# ESP32-C3_DEV-M-1.net
KiCad netlist of a schematic drawn in Altium Designer
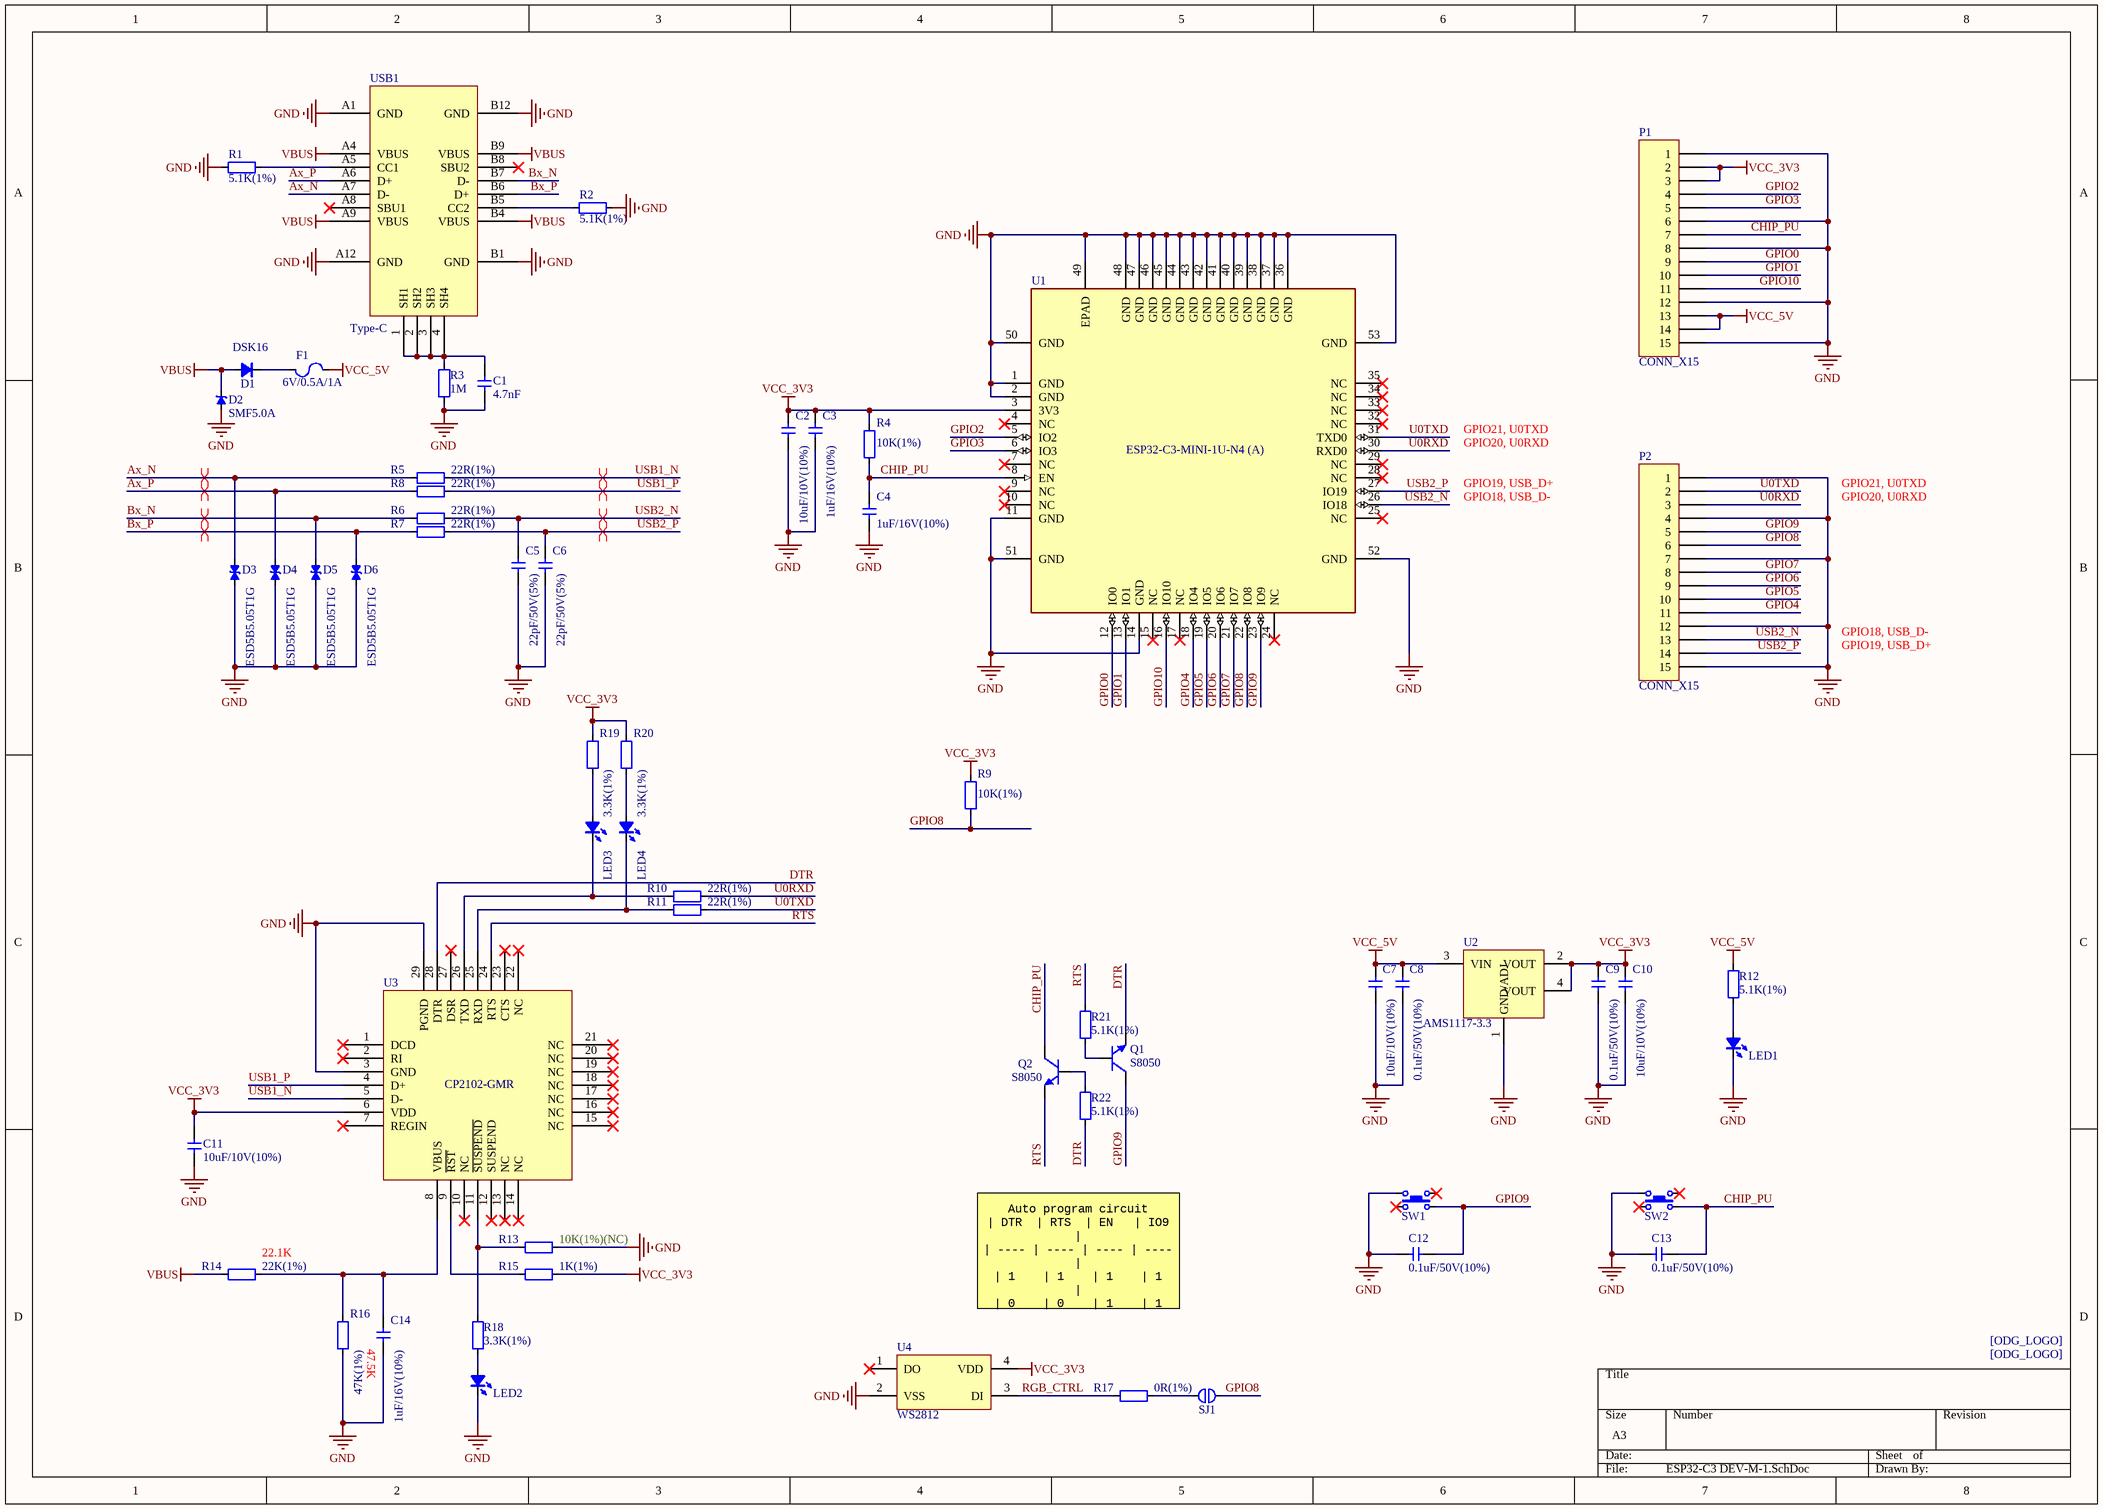
[diagram p0: ESP32-C3 DEV-M-1.SchDoc]

(export (version "E")
  (design (tool "Eeschema 10.0.6"))
  (components
    (comp (ref "C1")
      (value "4.7nF")
      (footprint "C0402")
      (description "Capacitor")
      (libsource (lib "ODG_AD_Lib") (part "CAP"))
    )
    (comp (ref "C2")
      (value "10uF/10V(10%)")
      (footprint "C0603")
      (description "Capacitor")
      (libsource (lib "ODG_AD_Lib") (part "CAP"))
    )
    (comp (ref "C3")
      (value "1uF/16V(10%)")
      (footprint "C0402")
      (description "Capacitor")
      (libsource (lib "ODG_AD_Lib") (part "CAP"))
    )
    (comp (ref "C4")
      (value "1uF/16V(10%)")
      (footprint "C0402")
      (description "Capacitor")
      (libsource (lib "ODG_AD_Lib") (part "CAP"))
    )
    (comp (ref "C5")
      (value "22pF/50V(5%)")
      (footprint "C0402")
      (description "Capacitor")
      (libsource (lib "ODG_AD_Lib") (part "CAP"))
    )
    (comp (ref "C6")
      (value "22pF/50V(5%)")
      (footprint "C0402")
      (description "Capacitor")
      (libsource (lib "ODG_AD_Lib") (part "CAP"))
    )
    (comp (ref "C7")
      (value "10uF/10V(10%)")
      (footprint "C0603")
      (description "Capacitor")
      (libsource (lib "ODG_AD_Lib") (part "CAP"))
    )
    (comp (ref "C8")
      (value "0.1uF/50V(10%)")
      (footprint "C0402")
      (description "Capacitor")
      (libsource (lib "ODG_AD_Lib") (part "CAP"))
    )
    (comp (ref "C9")
      (value "0.1uF/50V(10%)")
      (footprint "C0402")
      (description "Capacitor")
      (libsource (lib "ODG_AD_Lib") (part "CAP"))
    )
    (comp (ref "C10")
      (value "10uF/10V(10%)")
      (footprint "C0603")
      (description "Capacitor")
      (libsource (lib "ODG_AD_Lib") (part "CAP"))
    )
    (comp (ref "C11")
      (value "10uF/10V(10%)")
      (footprint "C0603")
      (description "Capacitor")
      (libsource (lib "ODG_AD_Lib") (part "CAP"))
    )
    (comp (ref "C12")
      (value "0.1uF/50V(10%)")
      (footprint "C0402")
      (description "Capacitor")
      (libsource (lib "ODG_AD_Lib") (part "CAP"))
    )
    (comp (ref "C13")
      (value "0.1uF/50V(10%)")
      (footprint "C0402")
      (description "Capacitor")
      (libsource (lib "ODG_AD_Lib") (part "CAP"))
    )
    (comp (ref "C14")
      (value "1uF/16V(10%)")
      (footprint "C0402")
      (description "Capacitor")
      (libsource (lib "ODG_AD_Lib") (part "CAP"))
    )
    (comp (ref "D1")
      (value "DSK16")
      (footprint "SOD123F")
      (description "二极管")
      (libsource (lib "ODG_AD_Lib") (part "DIODE"))
    )
    (comp (ref "D2")
      (value "SMF5.0A")
      (footprint "SOD123F")
      (description "极性：Unidirectional")
      (fields
        (field (name "MF") "Taiwan Semiconductor Corporation")
        (field (name "DIGI-KEY_PART_NUMBER") "TESD5V0L1UCRJGTR-ND")
      )
      (libsource (lib "ODG_AD_Lib") (part "TVS_U"))
    )
    (comp (ref "D3")
      (value "ESD5B5.05T1G")
      (footprint "SOD-523")
      (description "极性：Bidirectional")
      (fields
        (field (name "MF") "Taiwan Semiconductor Corporation")
        (field (name "DIGI-KEY_PART_NUMBER") "TESD5V0L1UCRJGTR-ND")
      )
      (libsource (lib "ODG_AD_Lib") (part "TVS_BI"))
    )
    (comp (ref "D4")
      (value "ESD5B5.05T1G")
      (footprint "SOD-523")
      (description "极性：Bidirectional")
      (fields
        (field (name "MF") "Taiwan Semiconductor Corporation")
        (field (name "DIGI-KEY_PART_NUMBER") "TESD5V0L1UCRJGTR-ND")
      )
      (libsource (lib "ODG_AD_Lib") (part "TVS_BI"))
    )
    (comp (ref "D5")
      (value "ESD5B5.05T1G")
      (footprint "SOD-523")
      (description "极性：Bidirectional")
      (fields
        (field (name "MF") "Taiwan Semiconductor Corporation")
        (field (name "DIGI-KEY_PART_NUMBER") "TESD5V0L1UCRJGTR-ND")
      )
      (libsource (lib "ODG_AD_Lib") (part "TVS_BI"))
    )
    (comp (ref "D6")
      (value "ESD5B5.05T1G")
      (footprint "SOD-523")
      (description "极性：Bidirectional")
      (fields
        (field (name "MF") "Taiwan Semiconductor Corporation")
        (field (name "DIGI-KEY_PART_NUMBER") "TESD5V0L1UCRJGTR-ND")
      )
      (libsource (lib "ODG_AD_Lib") (part "TVS_BI"))
    )
    (comp (ref "F1")
      (value "6V/0.5A/1A")
      (footprint "FUSE0603_0.5MM")
      (description "贴片自恢复保险丝")
      (libsource (lib "ODG_AD_Lib") (part "FUSE"))
    )
    (comp (ref "LED1") (value "LED") (footprint "LED0603_RED") (libsource (lib "ODG_AD_Lib") (part "LED")))
    (comp (ref "LED2") (value "LED") (footprint "LED0603_RED") (libsource (lib "ODG_AD_Lib") (part "LED")))
    (comp (ref "LED3") (value "LED") (footprint "LED0603_RED") (libsource (lib "ODG_AD_Lib") (part "LED")))
    (comp (ref "LED4") (value "LED") (footprint "LED0603_RED") (libsource (lib "ODG_AD_Lib") (part "LED")))
    (comp (ref "ODG1")
      (value "ODG_LOGO")
      (footprint "ODG_LOGO")
      (libsource (lib "ODG_AD_Lib") (part "ODG_LOGO"))
    )
    (comp (ref "ODG2")
      (value "ODG_LOGO")
      (footprint "ODG_LOGO")
      (libsource (lib "ODG_AD_Lib") (part "ODG_LOGO"))
    )
    (comp (ref "P1")
      (value "CONN_X15")
      (footprint "2.54MM_MALE_X15")
      (libsource (lib "ODG_AD_Lib") (part "CONN_X15"))
    )
    (comp (ref "P2")
      (value "CONN_X15")
      (footprint "2.54MM_MALE_X15")
      (libsource (lib "ODG_AD_Lib") (part "CONN_X15"))
    )
    (comp (ref "Q1")
      (value "S8050")
      (footprint "INFINEON SOT-23-3")
      (description "NPN型")
      (libsource (lib "ODG_AD_Lib") (part "NPN"))
    )
    (comp (ref "Q2")
      (value "S8050")
      (footprint "INFINEON SOT-23-3")
      (description "NPN型")
      (libsource (lib "ODG_AD_Lib") (part "NPN"))
    )
    (comp (ref "R1")
      (value "5.1K(1%)")
      (footprint "R0402")
      (description "Resistor")
      (libsource (lib "") (part "RES_1"))
    )
    (comp (ref "R2")
      (value "5.1K(1%)")
      (footprint "R0402")
      (description "Resistor")
      (libsource (lib "") (part "RES_1"))
    )
    (comp (ref "R3")
      (value "1M")
      (footprint "R0402")
      (description "Resistor")
      (libsource (lib "ODG_AD_Lib") (part "RES"))
    )
    (comp (ref "R4")
      (value "10K(1%)")
      (footprint "R0402")
      (description "Resistor")
      (libsource (lib "") (part "RES_1"))
    )
    (comp (ref "R5")
      (value "22R(1%)")
      (footprint "R0402")
      (description "Resistor")
      (libsource (lib "ODG_AD_Lib") (part "RES"))
    )
    (comp (ref "R6")
      (value "22R(1%)")
      (footprint "R0402")
      (description "Resistor")
      (libsource (lib "ODG_AD_Lib") (part "RES"))
    )
    (comp (ref "R7")
      (value "22R(1%)")
      (footprint "R0402")
      (description "Resistor")
      (libsource (lib "ODG_AD_Lib") (part "RES"))
    )
    (comp (ref "R8")
      (value "22R(1%)")
      (footprint "R0402")
      (description "Resistor")
      (libsource (lib "ODG_AD_Lib") (part "RES"))
    )
    (comp (ref "R9")
      (value "10K(1%)")
      (footprint "R0402")
      (description "Resistor")
      (libsource (lib "") (part "RES_1"))
    )
    (comp (ref "R10")
      (value "22R(1%)")
      (footprint "R0402")
      (description "Resistor")
      (libsource (lib "ODG_AD_Lib") (part "RES"))
    )
    (comp (ref "R11")
      (value "22R(1%)")
      (footprint "R0402")
      (description "Resistor")
      (libsource (lib "ODG_AD_Lib") (part "RES"))
    )
    (comp (ref "R12")
      (value "5.1K(1%)")
      (footprint "R0402")
      (description "Resistor")
      (libsource (lib "") (part "RES_1"))
    )
    (comp (ref "R13")
      (value "10K(1%)(NC)")
      (footprint "R0402")
      (description "Resistor")
      (libsource (lib "ODG_AD_Lib") (part "RES"))
    )
    (comp (ref "R14")
      (value "22K(1%)")
      (footprint "R0402")
      (description "Resistor")
      (libsource (lib "ODG_AD_Lib") (part "RES"))
    )
    (comp (ref "R15")
      (value "1K(1%)")
      (footprint "R0402")
      (description "Resistor")
      (libsource (lib "ODG_AD_Lib") (part "RES"))
    )
    (comp (ref "R16")
      (value "47K(1%)")
      (footprint "R0402")
      (description "Resistor")
      (libsource (lib "") (part "RES_1"))
    )
    (comp (ref "R17")
      (value "0R(1%)")
      (footprint "R0402")
      (description "Resistor")
      (libsource (lib "ODG_AD_Lib") (part "RES"))
    )
    (comp (ref "R18")
      (value "3.3K(1%)")
      (footprint "R0402")
      (description "Resistor")
      (libsource (lib "") (part "RES_1"))
    )
    (comp (ref "R19")
      (value "3.3K(1%)")
      (footprint "R0402")
      (description "Resistor")
      (libsource (lib "") (part "RES_1"))
    )
    (comp (ref "R20")
      (value "3.3K(1%)")
      (footprint "R0402")
      (description "Resistor")
      (libsource (lib "") (part "RES_1"))
    )
    (comp (ref "R21")
      (value "5.1K(1%)")
      (footprint "R0402")
      (description "Resistor")
      (libsource (lib "") (part "RES_1"))
    )
    (comp (ref "R22")
      (value "5.1K(1%)")
      (footprint "R0402")
      (description "Resistor")
      (libsource (lib "") (part "RES_1"))
    )
    (comp (ref "SJ1")
      (value "SJ_2P")
      (footprint "SJ_2P_MINI")
      (description "焊接跳线")
      (libsource (lib "ODG_AD_Lib") (part "SJ_2P"))
    )
    (comp (ref "SW1")
      (value "Button-4P")
      (footprint "SWITCH_3X4X2.5_4PIN_SMD")
      (description "Button")
      (libsource (lib "ODG_AD_Lib") (part "Button-4P"))
    )
    (comp (ref "SW2")
      (value "Button-4P")
      (footprint "SWITCH_3X4X2.5_4PIN_SMD")
      (description "Button")
      (libsource (lib "ODG_AD_Lib") (part "Button-4P"))
    )
    (comp (ref "U1")
      (value "ESP32-C3-MINI-1U-N4 (A)")
      (footprint "XCVR_ESP32-C3-MINI-1U-N4")
      (fields
        (field (name "MF") "Espressif Systems")
        (field (name "DIGI-KEY_PART_NUMBER") "1965-ESP32-C3-MINI-1U-N4TR-ND")
        (field (name "MP") "ESP32-C3-MINI-1U-N4")
      )
      (libsource (lib "ODG_AD_Lib") (part "ESP32-C3-MINI-1U-N4 (A)"))
    )
    (comp (ref "U2")
      (value "AMS1117-3.3")
      (footprint "TI SOT-223 DCY")
      (description "线性稳压芯片")
      (libsource (lib "ODG_AD_Lib") (part "AMS1117"))
    )
    (comp (ref "U3")
      (value "CP2102-GMR")
      (footprint "QFN-28_EP")
      (description "USB转TTL")
      (fields (field (name "PART NUMBER") "CP2102"))
      (libsource (lib "ODG_AD_Lib") (part "CP2102 QFN28 (A)"))
    )
    (comp (ref "U4")
      (value "WS2812")
      (footprint "WS2812_2020")
      (libsource (lib "ODG_AD_Lib") (part "WS2812"))
    )
    (comp (ref "USB1")
      (value "Type-C")
      (footprint "Type-C-TOP")
      (libsource (lib "ODG_AD_Lib") (part "USB-Type-C_16P"))
    )
  )
  (nets
    (net (code "1") (name "/Ax_N") (class "Default")
      (node (ref "D3") (pin "2") (pinfunction "2_2") (pintype "passive"))
      (node (ref "R5") (pin "2") (pinfunction "2_2") (pintype "passive"))
      (node (ref "USB1") (pin "A7") (pinfunction "D-_A7") (pintype "passive"))
    )
    (net (code "2") (name "/Ax_P") (class "Default")
      (node (ref "D4") (pin "2") (pinfunction "2_2") (pintype "passive"))
      (node (ref "R8") (pin "2") (pinfunction "2_2") (pintype "passive"))
      (node (ref "USB1") (pin "A6") (pinfunction "D+_A6") (pintype "passive"))
    )
    (net (code "3") (name "/Bx_N") (class "Default")
      (node (ref "D5") (pin "2") (pinfunction "2_2") (pintype "passive"))
      (node (ref "R6") (pin "2") (pinfunction "2_2") (pintype "passive"))
      (node (ref "USB1") (pin "B7") (pinfunction "D-_B7") (pintype "passive"))
    )
    (net (code "4") (name "/Bx_P") (class "Default")
      (node (ref "D6") (pin "2") (pinfunction "2_2") (pintype "passive"))
      (node (ref "R7") (pin "2") (pinfunction "2_2") (pintype "passive"))
      (node (ref "USB1") (pin "B6") (pinfunction "D+_B6") (pintype "passive"))
    )
    (net (code "5") (name "/CHIP_PU") (class "Default")
      (node (ref "C13") (pin "1") (pinfunction "1_1") (pintype "passive"))
      (node (ref "C4") (pin "2") (pinfunction "2_2") (pintype "passive"))
      (node (ref "P1") (pin "7") (pinfunction "7_7") (pintype "passive"))
      (node (ref "Q2") (pin "3") (pinfunction "C_3") (pintype "passive"))
      (node (ref "R4") (pin "1") (pinfunction "1_1") (pintype "passive"))
      (node (ref "SW2") (pin "4") (pinfunction "4_4") (pintype "passive"))
      (node (ref "U1") (pin "8") (pinfunction "EN_8") (pintype "input"))
    )
    (net (code "6") (name "/DTR") (class "Default")
      (node (ref "Q1") (pin "2") (pinfunction "E_2") (pintype "passive"))
      (node (ref "R22") (pin "1") (pinfunction "1_1") (pintype "passive"))
      (node (ref "U3") (pin "28") (pinfunction "DTR_28") (pintype "passive"))
    )
    (net (code "7") (name "/GPIO0") (class "Default")
      (node (ref "P1") (pin "9") (pinfunction "9_9") (pintype "passive"))
      (node (ref "U1") (pin "12") (pinfunction "IO0_12") (pintype "bidirectional"))
    )
    (net (code "8") (name "/GPIO1") (class "Default")
      (node (ref "P1") (pin "10") (pinfunction "10_10") (pintype "passive"))
      (node (ref "U1") (pin "13") (pinfunction "IO1_13") (pintype "bidirectional"))
    )
    (net (code "9") (name "/GPIO2") (class "Default")
      (node (ref "P1") (pin "4") (pinfunction "4_4") (pintype "passive"))
      (node (ref "U1") (pin "5") (pinfunction "IO2_5") (pintype "bidirectional"))
    )
    (net (code "10") (name "/GPIO3") (class "Default")
      (node (ref "P1") (pin "5") (pinfunction "5_5") (pintype "passive"))
      (node (ref "U1") (pin "6") (pinfunction "IO3_6") (pintype "bidirectional"))
    )
    (net (code "11") (name "/GPIO4") (class "Default")
      (node (ref "P2") (pin "11") (pinfunction "11_11") (pintype "passive"))
      (node (ref "U1") (pin "18") (pinfunction "IO4_18") (pintype "bidirectional"))
    )
    (net (code "12") (name "/GPIO5") (class "Default")
      (node (ref "P2") (pin "10") (pinfunction "10_10") (pintype "passive"))
      (node (ref "U1") (pin "19") (pinfunction "IO5_19") (pintype "bidirectional"))
    )
    (net (code "13") (name "/GPIO6") (class "Default")
      (node (ref "P2") (pin "9") (pinfunction "9_9") (pintype "passive"))
      (node (ref "U1") (pin "20") (pinfunction "IO6_20") (pintype "bidirectional"))
    )
    (net (code "14") (name "/GPIO7") (class "Default")
      (node (ref "P2") (pin "8") (pinfunction "8_8") (pintype "passive"))
      (node (ref "U1") (pin "21") (pinfunction "IO7_21") (pintype "bidirectional"))
    )
    (net (code "15") (name "/GPIO8") (class "Default")
      (node (ref "P2") (pin "6") (pinfunction "6_6") (pintype "passive"))
      (node (ref "R9") (pin "1") (pinfunction "1_1") (pintype "passive"))
      (node (ref "SJ1") (pin "2") (pinfunction "2_2") (pintype "passive"))
      (node (ref "U1") (pin "22") (pinfunction "IO8_22") (pintype "bidirectional"))
    )
    (net (code "16") (name "/GPIO9") (class "Default")
      (node (ref "C12") (pin "1") (pinfunction "1_1") (pintype "passive"))
      (node (ref "P2") (pin "5") (pinfunction "5_5") (pintype "passive"))
      (node (ref "Q1") (pin "3") (pinfunction "C_3") (pintype "passive"))
      (node (ref "SW1") (pin "4") (pinfunction "4_4") (pintype "passive"))
      (node (ref "U1") (pin "23") (pinfunction "IO9_23") (pintype "bidirectional"))
    )
    (net (code "17") (name "/GPIO10") (class "Default")
      (node (ref "P1") (pin "11") (pinfunction "11_11") (pintype "passive"))
      (node (ref "U1") (pin "16") (pinfunction "IO10_16") (pintype "bidirectional"))
    )
    (net (code "18") (name "/RGB_CTRL") (class "Default")
      (node (ref "R17") (pin "2") (pinfunction "2_2") (pintype "passive"))
      (node (ref "U4") (pin "3") (pinfunction "DI_3") (pintype "passive"))
    )
    (net (code "19") (name "/RTS") (class "Default")
      (node (ref "Q2") (pin "2") (pinfunction "E_2") (pintype "passive"))
      (node (ref "R21") (pin "2") (pinfunction "2_2") (pintype "passive"))
      (node (ref "U3") (pin "24") (pinfunction "RTS_24") (pintype "passive"))
    )
    (net (code "20") (name "/U0RXD") (class "Default")
      (node (ref "P2") (pin "3") (pinfunction "3_3") (pintype "passive"))
      (node (ref "R10") (pin "1") (pinfunction "1_1") (pintype "passive"))
      (node (ref "U1") (pin "30") (pinfunction "RXD0_30") (pintype "bidirectional"))
    )
    (net (code "21") (name "/U0TXD") (class "Default")
      (node (ref "P2") (pin "2") (pinfunction "2_2") (pintype "passive"))
      (node (ref "R11") (pin "1") (pinfunction "1_1") (pintype "passive"))
      (node (ref "U1") (pin "31") (pinfunction "TXD0_31") (pintype "bidirectional"))
    )
    (net (code "22") (name "/USB1_N") (class "Default")
      (node (ref "R5") (pin "1") (pinfunction "1_1") (pintype "passive"))
      (node (ref "U3") (pin "5") (pinfunction "D-_5") (pintype "passive"))
    )
    (net (code "23") (name "/USB1_P") (class "Default")
      (node (ref "R8") (pin "1") (pinfunction "1_1") (pintype "passive"))
      (node (ref "U3") (pin "4") (pinfunction "D+_4") (pintype "passive"))
    )
    (net (code "24") (name "/USB2_N") (class "Default")
      (node (ref "C5") (pin "2") (pinfunction "2_2") (pintype "passive"))
      (node (ref "P2") (pin "13") (pinfunction "13_13") (pintype "passive"))
      (node (ref "R6") (pin "1") (pinfunction "1_1") (pintype "passive"))
      (node (ref "U1") (pin "26") (pinfunction "IO18_26") (pintype "bidirectional"))
    )
    (net (code "25") (name "/USB2_P") (class "Default")
      (node (ref "C6") (pin "2") (pinfunction "2_2") (pintype "passive"))
      (node (ref "P2") (pin "14") (pinfunction "14_14") (pintype "passive"))
      (node (ref "R7") (pin "1") (pinfunction "1_1") (pintype "passive"))
      (node (ref "U1") (pin "27") (pinfunction "IO19_27") (pintype "bidirectional"))
    )
    (net (code "26") (name "GND") (class "Default")
      (node (ref "C1") (pin "2") (pinfunction "2_2") (pintype "passive"))
      (node (ref "C10") (pin "1") (pinfunction "1_1") (pintype "passive"))
      (node (ref "C11") (pin "1") (pinfunction "1_1") (pintype "passive"))
      (node (ref "C12") (pin "2") (pinfunction "2_2") (pintype "passive"))
      (node (ref "C13") (pin "2") (pinfunction "2_2") (pintype "passive"))
      (node (ref "C14") (pin "1") (pinfunction "1_1") (pintype "passive"))
      (node (ref "C2") (pin "1") (pinfunction "1_1") (pintype "passive"))
      (node (ref "C3") (pin "1") (pinfunction "1_1") (pintype "passive"))
      (node (ref "C4") (pin "1") (pinfunction "1_1") (pintype "passive"))
      (node (ref "C5") (pin "1") (pinfunction "1_1") (pintype "passive"))
      (node (ref "C6") (pin "1") (pinfunction "1_1") (pintype "passive"))
      (node (ref "C7") (pin "1") (pinfunction "1_1") (pintype "passive"))
      (node (ref "C8") (pin "1") (pinfunction "1_1") (pintype "passive"))
      (node (ref "C9") (pin "1") (pinfunction "1_1") (pintype "passive"))
      (node (ref "D2") (pin "1") (pinfunction "1_1") (pintype "passive"))
      (node (ref "D3") (pin "1") (pinfunction "1_1") (pintype "passive"))
      (node (ref "D4") (pin "1") (pinfunction "1_1") (pintype "passive"))
      (node (ref "D5") (pin "1") (pinfunction "1_1") (pintype "passive"))
      (node (ref "D6") (pin "1") (pinfunction "1_1") (pintype "passive"))
      (node (ref "LED1") (pin "2") (pinfunction "K_2") (pintype "passive"))
      (node (ref "LED2") (pin "2") (pinfunction "K_2") (pintype "passive"))
      (node (ref "P1") (pin "1") (pinfunction "1_1") (pintype "passive"))
      (node (ref "P1") (pin "12") (pinfunction "12_12") (pintype "passive"))
      (node (ref "P1") (pin "15") (pinfunction "15_15") (pintype "passive"))
      (node (ref "P1") (pin "6") (pinfunction "6_6") (pintype "passive"))
      (node (ref "P1") (pin "8") (pinfunction "8_8") (pintype "passive"))
      (node (ref "P2") (pin "1") (pinfunction "1_1") (pintype "passive"))
      (node (ref "P2") (pin "12") (pinfunction "12_12") (pintype "passive"))
      (node (ref "P2") (pin "15") (pinfunction "15_15") (pintype "passive"))
      (node (ref "P2") (pin "4") (pinfunction "4_4") (pintype "passive"))
      (node (ref "P2") (pin "7") (pinfunction "7_7") (pintype "passive"))
      (node (ref "R1") (pin "1") (pinfunction "1_1") (pintype "passive"))
      (node (ref "R13") (pin "1") (pinfunction "1_1") (pintype "passive"))
      (node (ref "R16") (pin "1") (pinfunction "1_1") (pintype "passive"))
      (node (ref "R2") (pin "2") (pinfunction "2_2") (pintype "passive"))
      (node (ref "R3") (pin "2") (pinfunction "2_2") (pintype "passive"))
      (node (ref "SW1") (pin "1") (pinfunction "1_1") (pintype "passive"))
      (node (ref "SW2") (pin "1") (pinfunction "1_1") (pintype "passive"))
      (node (ref "U1") (pin "1") (pinfunction "GND_1") (pintype "power_in"))
      (node (ref "U1") (pin "11") (pinfunction "GND_11") (pintype "power_in"))
      (node (ref "U1") (pin "14") (pinfunction "GND_14") (pintype "power_in"))
      (node (ref "U1") (pin "2") (pinfunction "GND_2") (pintype "power_in"))
      (node (ref "U1") (pin "36") (pinfunction "GND_36") (pintype "power_in"))
      (node (ref "U1") (pin "37") (pinfunction "GND_37") (pintype "power_in"))
      (node (ref "U1") (pin "38") (pinfunction "GND_38") (pintype "power_in"))
      (node (ref "U1") (pin "39") (pinfunction "GND_39") (pintype "power_in"))
      (node (ref "U1") (pin "40") (pinfunction "GND_40") (pintype "power_in"))
      (node (ref "U1") (pin "41") (pinfunction "GND_41") (pintype "power_in"))
      (node (ref "U1") (pin "42") (pinfunction "GND_42") (pintype "power_in"))
      (node (ref "U1") (pin "43") (pinfunction "GND_43") (pintype "power_in"))
      (node (ref "U1") (pin "44") (pinfunction "GND_44") (pintype "power_in"))
      (node (ref "U1") (pin "45") (pinfunction "GND_45") (pintype "power_in"))
      (node (ref "U1") (pin "46") (pinfunction "GND_46") (pintype "power_in"))
      (node (ref "U1") (pin "47") (pinfunction "GND_47") (pintype "power_in"))
      (node (ref "U1") (pin "48") (pinfunction "GND_48") (pintype "power_in"))
      (node (ref "U1") (pin "49") (pinfunction "EPAD_49") (pintype "power_in"))
      (node (ref "U1") (pin "50") (pinfunction "GND_50") (pintype "power_in"))
      (node (ref "U1") (pin "51") (pinfunction "GND_51") (pintype "power_in"))
      (node (ref "U1") (pin "52") (pinfunction "GND_52") (pintype "power_in"))
      (node (ref "U1") (pin "53") (pinfunction "GND_53") (pintype "power_in"))
      (node (ref "U2") (pin "1") (pinfunction "GND/ADJ_1") (pintype "passive"))
      (node (ref "U3") (pin "29") (pinfunction "PGND_29") (pintype "passive"))
      (node (ref "U3") (pin "3") (pinfunction "GND_3") (pintype "passive"))
      (node (ref "U4") (pin "2") (pinfunction "VSS_2") (pintype "passive"))
      (node (ref "USB1") (pin "A1") (pinfunction "GND_A1") (pintype "passive"))
      (node (ref "USB1") (pin "A12") (pinfunction "GND_A12") (pintype "passive"))
      (node (ref "USB1") (pin "B1") (pinfunction "GND_B1") (pintype "passive"))
      (node (ref "USB1") (pin "B12") (pinfunction "GND_B12") (pintype "passive"))
    )
    (net (code "27") (name "Net-(D1-C)") (class "Default")
      (node (ref "D1") (pin "2") (pinfunction "C_2") (pintype "passive"))
      (node (ref "F1") (pin "1") (pinfunction "1_1") (pintype "passive"))
    )
    (net (code "28") (name "Net-(LED1-A)") (class "Default")
      (node (ref "LED1") (pin "1") (pinfunction "A_1") (pintype "passive"))
      (node (ref "R12") (pin "1") (pinfunction "1_1") (pintype "passive"))
    )
    (net (code "29") (name "Net-(LED2-A)") (class "Default")
      (node (ref "LED2") (pin "1") (pinfunction "A_1") (pintype "passive"))
      (node (ref "R18") (pin "1") (pinfunction "1_1") (pintype "passive"))
    )
    (net (code "30") (name "Net-(LED3-A)") (class "Default")
      (node (ref "LED3") (pin "1") (pinfunction "A_1") (pintype "passive"))
      (node (ref "R19") (pin "1") (pinfunction "1_1") (pintype "passive"))
    )
    (net (code "31") (name "Net-(LED3-K)") (class "Default")
      (node (ref "LED3") (pin "2") (pinfunction "K_2") (pintype "passive"))
      (node (ref "R10") (pin "2") (pinfunction "2_2") (pintype "passive"))
      (node (ref "U3") (pin "26") (pinfunction "TXD_26") (pintype "passive"))
    )
    (net (code "32") (name "Net-(LED4-A)") (class "Default")
      (node (ref "LED4") (pin "1") (pinfunction "A_1") (pintype "passive"))
      (node (ref "R20") (pin "1") (pinfunction "1_1") (pintype "passive"))
    )
    (net (code "33") (name "Net-(LED4-K)") (class "Default")
      (node (ref "LED4") (pin "2") (pinfunction "K_2") (pintype "passive"))
      (node (ref "R11") (pin "2") (pinfunction "2_2") (pintype "passive"))
      (node (ref "U3") (pin "25") (pinfunction "RXD_25") (pintype "passive"))
    )
    (net (code "34") (name "Net-(Q1-B)") (class "Default")
      (node (ref "Q1") (pin "1") (pinfunction "B_1") (pintype "passive"))
      (node (ref "R21") (pin "1") (pinfunction "1_1") (pintype "passive"))
    )
    (net (code "35") (name "Net-(Q2-B)") (class "Default")
      (node (ref "Q2") (pin "1") (pinfunction "B_1") (pintype "passive"))
      (node (ref "R22") (pin "2") (pinfunction "2_2") (pintype "passive"))
    )
    (net (code "36") (name "Net-(R17-Pad1)") (class "Default")
      (node (ref "R17") (pin "1") (pinfunction "1_1") (pintype "passive"))
      (node (ref "SJ1") (pin "1") (pinfunction "1_1") (pintype "passive"))
    )
    (net (code "37") (name "Net-(U3-VBUS)") (class "Default")
      (node (ref "C14") (pin "2") (pinfunction "2_2") (pintype "passive"))
      (node (ref "R14") (pin "1") (pinfunction "1_1") (pintype "passive"))
      (node (ref "R16") (pin "2") (pinfunction "2_2") (pintype "passive"))
      (node (ref "U3") (pin "8") (pinfunction "VBUS_8") (pintype "passive"))
    )
    (net (code "38") (name "Net-(U3-~{RST})") (class "Default")
      (node (ref "R15") (pin "2") (pinfunction "2_2") (pintype "passive"))
      (node (ref "U3") (pin "9") (pinfunction "~{RST}_9") (pintype "passive"))
    )
    (net (code "39") (name "Net-(U3-~{SUSPEND})") (class "Default")
      (node (ref "R13") (pin "2") (pinfunction "2_2") (pintype "passive"))
      (node (ref "R18") (pin "2") (pinfunction "2_2") (pintype "passive"))
      (node (ref "U3") (pin "11") (pinfunction "~{SUSPEND}_11") (pintype "passive"))
    )
    (net (code "40") (name "Net-(USB1-CC1)") (class "Default")
      (node (ref "R1") (pin "2") (pinfunction "2_2") (pintype "passive"))
      (node (ref "USB1") (pin "A5") (pinfunction "CC1_A5") (pintype "passive"))
    )
    (net (code "41") (name "Net-(USB1-CC2)") (class "Default")
      (node (ref "R2") (pin "1") (pinfunction "1_1") (pintype "passive"))
      (node (ref "USB1") (pin "B5") (pinfunction "CC2_B5") (pintype "passive"))
    )
    (net (code "42") (name "Net-(USB1-SH1)") (class "Default")
      (node (ref "C1") (pin "1") (pinfunction "1_1") (pintype "passive"))
      (node (ref "R3") (pin "1") (pinfunction "1_1") (pintype "passive"))
      (node (ref "USB1") (pin "1") (pinfunction "SH1_1") (pintype "passive"))
      (node (ref "USB1") (pin "2") (pinfunction "SH2_2") (pintype "passive"))
      (node (ref "USB1") (pin "3") (pinfunction "SH3_3") (pintype "passive"))
      (node (ref "USB1") (pin "4") (pinfunction "SH4_4") (pintype "passive"))
    )
    (net (code "43") (name "VBUS") (class "Default")
      (node (ref "D1") (pin "1") (pinfunction "A_1") (pintype "passive"))
      (node (ref "D2") (pin "2") (pinfunction "2_2") (pintype "passive"))
      (node (ref "R14") (pin "2") (pinfunction "2_2") (pintype "passive"))
      (node (ref "USB1") (pin "A4") (pinfunction "VBUS_A4") (pintype "passive"))
      (node (ref "USB1") (pin "A9") (pinfunction "VBUS_A9") (pintype "passive"))
      (node (ref "USB1") (pin "B4") (pinfunction "VBUS_B4") (pintype "passive"))
      (node (ref "USB1") (pin "B9") (pinfunction "VBUS_B9") (pintype "passive"))
    )
    (net (code "44") (name "VCC_3V3") (class "Default")
      (node (ref "C10") (pin "2") (pinfunction "2_2") (pintype "passive"))
      (node (ref "C11") (pin "2") (pinfunction "2_2") (pintype "passive"))
      (node (ref "C2") (pin "2") (pinfunction "2_2") (pintype "passive"))
      (node (ref "C3") (pin "2") (pinfunction "2_2") (pintype "passive"))
      (node (ref "C9") (pin "2") (pinfunction "2_2") (pintype "passive"))
      (node (ref "P1") (pin "2") (pinfunction "2_2") (pintype "passive"))
      (node (ref "P1") (pin "3") (pinfunction "3_3") (pintype "passive"))
      (node (ref "R15") (pin "1") (pinfunction "1_1") (pintype "passive"))
      (node (ref "R19") (pin "2") (pinfunction "2_2") (pintype "passive"))
      (node (ref "R20") (pin "2") (pinfunction "2_2") (pintype "passive"))
      (node (ref "R4") (pin "2") (pinfunction "2_2") (pintype "passive"))
      (node (ref "R9") (pin "2") (pinfunction "2_2") (pintype "passive"))
      (node (ref "U1") (pin "3") (pinfunction "3V3_3") (pintype "power_in"))
      (node (ref "U2") (pin "2") (pinfunction "VOUT_2") (pintype "passive"))
      (node (ref "U2") (pin "4") (pinfunction "VOUT_4") (pintype "passive"))
      (node (ref "U3") (pin "6") (pinfunction "VDD_6") (pintype "passive"))
      (node (ref "U4") (pin "4") (pinfunction "VDD_4") (pintype "passive"))
    )
    (net (code "45") (name "VCC_5V") (class "Default")
      (node (ref "C7") (pin "2") (pinfunction "2_2") (pintype "passive"))
      (node (ref "C8") (pin "2") (pinfunction "2_2") (pintype "passive"))
      (node (ref "F1") (pin "2") (pinfunction "2_2") (pintype "passive"))
      (node (ref "P1") (pin "13") (pinfunction "13_13") (pintype "passive"))
      (node (ref "P1") (pin "14") (pinfunction "14_14") (pintype "passive"))
      (node (ref "R12") (pin "2") (pinfunction "2_2") (pintype "passive"))
      (node (ref "U2") (pin "3") (pinfunction "VIN_3") (pintype "passive"))
    )
    (net (code "46") (name "unconnected-(SW1-Pad2)") (class "Default")
      (node (ref "SW1") (pin "2") (pinfunction "2_2") (pintype "passive+no_connect"))
    )
    (net (code "47") (name "unconnected-(SW1-Pad3)") (class "Default")
      (node (ref "SW1") (pin "3") (pinfunction "3_3") (pintype "passive+no_connect"))
    )
    (net (code "48") (name "unconnected-(SW2-Pad2)") (class "Default")
      (node (ref "SW2") (pin "2") (pinfunction "2_2") (pintype "passive+no_connect"))
    )
    (net (code "49") (name "unconnected-(SW2-Pad3)") (class "Default")
      (node (ref "SW2") (pin "3") (pinfunction "3_3") (pintype "passive+no_connect"))
    )
    (net (code "50") (name "unconnected-(U1-NC-Pad4)") (class "Default")
      (node (ref "U1") (pin "4") (pinfunction "NC_4") (pintype "passive+no_connect"))
    )
    (net (code "51") (name "unconnected-(U1-NC-Pad7)") (class "Default")
      (node (ref "U1") (pin "7") (pinfunction "NC_7") (pintype "passive+no_connect"))
    )
    (net (code "52") (name "unconnected-(U1-NC-Pad9)") (class "Default")
      (node (ref "U1") (pin "9") (pinfunction "NC_9") (pintype "passive+no_connect"))
    )
    (net (code "53") (name "unconnected-(U1-NC-Pad10)") (class "Default")
      (node (ref "U1") (pin "10") (pinfunction "NC_10") (pintype "passive+no_connect"))
    )
    (net (code "54") (name "unconnected-(U1-NC-Pad15)") (class "Default")
      (node (ref "U1") (pin "15") (pinfunction "NC_15") (pintype "passive+no_connect"))
    )
    (net (code "55") (name "unconnected-(U1-NC-Pad17)") (class "Default")
      (node (ref "U1") (pin "17") (pinfunction "NC_17") (pintype "passive+no_connect"))
    )
    (net (code "56") (name "unconnected-(U1-NC-Pad24)") (class "Default")
      (node (ref "U1") (pin "24") (pinfunction "NC_24") (pintype "passive+no_connect"))
    )
    (net (code "57") (name "unconnected-(U1-NC-Pad25)") (class "Default")
      (node (ref "U1") (pin "25") (pinfunction "NC_25") (pintype "passive+no_connect"))
    )
    (net (code "58") (name "unconnected-(U1-NC-Pad28)") (class "Default")
      (node (ref "U1") (pin "28") (pinfunction "NC_28") (pintype "passive+no_connect"))
    )
    (net (code "59") (name "unconnected-(U1-NC-Pad29)") (class "Default")
      (node (ref "U1") (pin "29") (pinfunction "NC_29") (pintype "passive+no_connect"))
    )
    (net (code "60") (name "unconnected-(U1-NC-Pad32)") (class "Default")
      (node (ref "U1") (pin "32") (pinfunction "NC_32") (pintype "passive+no_connect"))
    )
    (net (code "61") (name "unconnected-(U1-NC-Pad33)") (class "Default")
      (node (ref "U1") (pin "33") (pinfunction "NC_33") (pintype "passive+no_connect"))
    )
    (net (code "62") (name "unconnected-(U1-NC-Pad34)") (class "Default")
      (node (ref "U1") (pin "34") (pinfunction "NC_34") (pintype "passive+no_connect"))
    )
    (net (code "63") (name "unconnected-(U1-NC-Pad35)") (class "Default")
      (node (ref "U1") (pin "35") (pinfunction "NC_35") (pintype "passive+no_connect"))
    )
    (net (code "64") (name "unconnected-(U3-CTS-Pad23)") (class "Default")
      (node (ref "U3") (pin "23") (pinfunction "CTS_23") (pintype "passive+no_connect"))
    )
    (net (code "65") (name "unconnected-(U3-DCD-Pad1)") (class "Default")
      (node (ref "U3") (pin "1") (pinfunction "DCD_1") (pintype "passive+no_connect"))
    )
    (net (code "66") (name "unconnected-(U3-DSR-Pad27)") (class "Default")
      (node (ref "U3") (pin "27") (pinfunction "DSR_27") (pintype "passive+no_connect"))
    )
    (net (code "67") (name "unconnected-(U3-NC-Pad10)") (class "Default")
      (node (ref "U3") (pin "10") (pinfunction "NC_10") (pintype "passive+no_connect"))
    )
    (net (code "68") (name "unconnected-(U3-NC-Pad13)") (class "Default")
      (node (ref "U3") (pin "13") (pinfunction "NC_13") (pintype "passive+no_connect"))
    )
    (net (code "69") (name "unconnected-(U3-NC-Pad14)") (class "Default")
      (node (ref "U3") (pin "14") (pinfunction "NC_14") (pintype "passive+no_connect"))
    )
    (net (code "70") (name "unconnected-(U3-NC-Pad15)") (class "Default")
      (node (ref "U3") (pin "15") (pinfunction "NC_15") (pintype "passive+no_connect"))
    )
    (net (code "71") (name "unconnected-(U3-NC-Pad16)") (class "Default")
      (node (ref "U3") (pin "16") (pinfunction "NC_16") (pintype "passive+no_connect"))
    )
    (net (code "72") (name "unconnected-(U3-NC-Pad17)") (class "Default")
      (node (ref "U3") (pin "17") (pinfunction "NC_17") (pintype "passive+no_connect"))
    )
    (net (code "73") (name "unconnected-(U3-NC-Pad18)") (class "Default")
      (node (ref "U3") (pin "18") (pinfunction "NC_18") (pintype "passive+no_connect"))
    )
    (net (code "74") (name "unconnected-(U3-NC-Pad19)") (class "Default")
      (node (ref "U3") (pin "19") (pinfunction "NC_19") (pintype "passive+no_connect"))
    )
    (net (code "75") (name "unconnected-(U3-NC-Pad20)") (class "Default")
      (node (ref "U3") (pin "20") (pinfunction "NC_20") (pintype "passive+no_connect"))
    )
    (net (code "76") (name "unconnected-(U3-NC-Pad21)") (class "Default")
      (node (ref "U3") (pin "21") (pinfunction "NC_21") (pintype "passive+no_connect"))
    )
    (net (code "77") (name "unconnected-(U3-NC-Pad22)") (class "Default")
      (node (ref "U3") (pin "22") (pinfunction "NC_22") (pintype "passive+no_connect"))
    )
    (net (code "78") (name "unconnected-(U3-REGIN-Pad7)") (class "Default")
      (node (ref "U3") (pin "7") (pinfunction "REGIN_7") (pintype "passive+no_connect"))
    )
    (net (code "79") (name "unconnected-(U3-RI-Pad2)") (class "Default")
      (node (ref "U3") (pin "2") (pinfunction "RI_2") (pintype "passive+no_connect"))
    )
    (net (code "80") (name "unconnected-(U3-SUSPEND-Pad12)") (class "Default")
      (node (ref "U3") (pin "12") (pinfunction "SUSPEND_12") (pintype "passive+no_connect"))
    )
    (net (code "81") (name "unconnected-(U4-DO-Pad1)") (class "Default")
      (node (ref "U4") (pin "1") (pinfunction "DO_1") (pintype "passive+no_connect"))
    )
    (net (code "82") (name "unconnected-(USB1-SBU1-PadA8)") (class "Default")
      (node (ref "USB1") (pin "A8") (pinfunction "SBU1_A8") (pintype "passive+no_connect"))
    )
    (net (code "83") (name "unconnected-(USB1-SBU2-PadB8)") (class "Default")
      (node (ref "USB1") (pin "B8") (pinfunction "SBU2_B8") (pintype "passive+no_connect"))
    )
  )
)
